# DAC.net
KiCad netlist of a schematic drawn in EAGLE
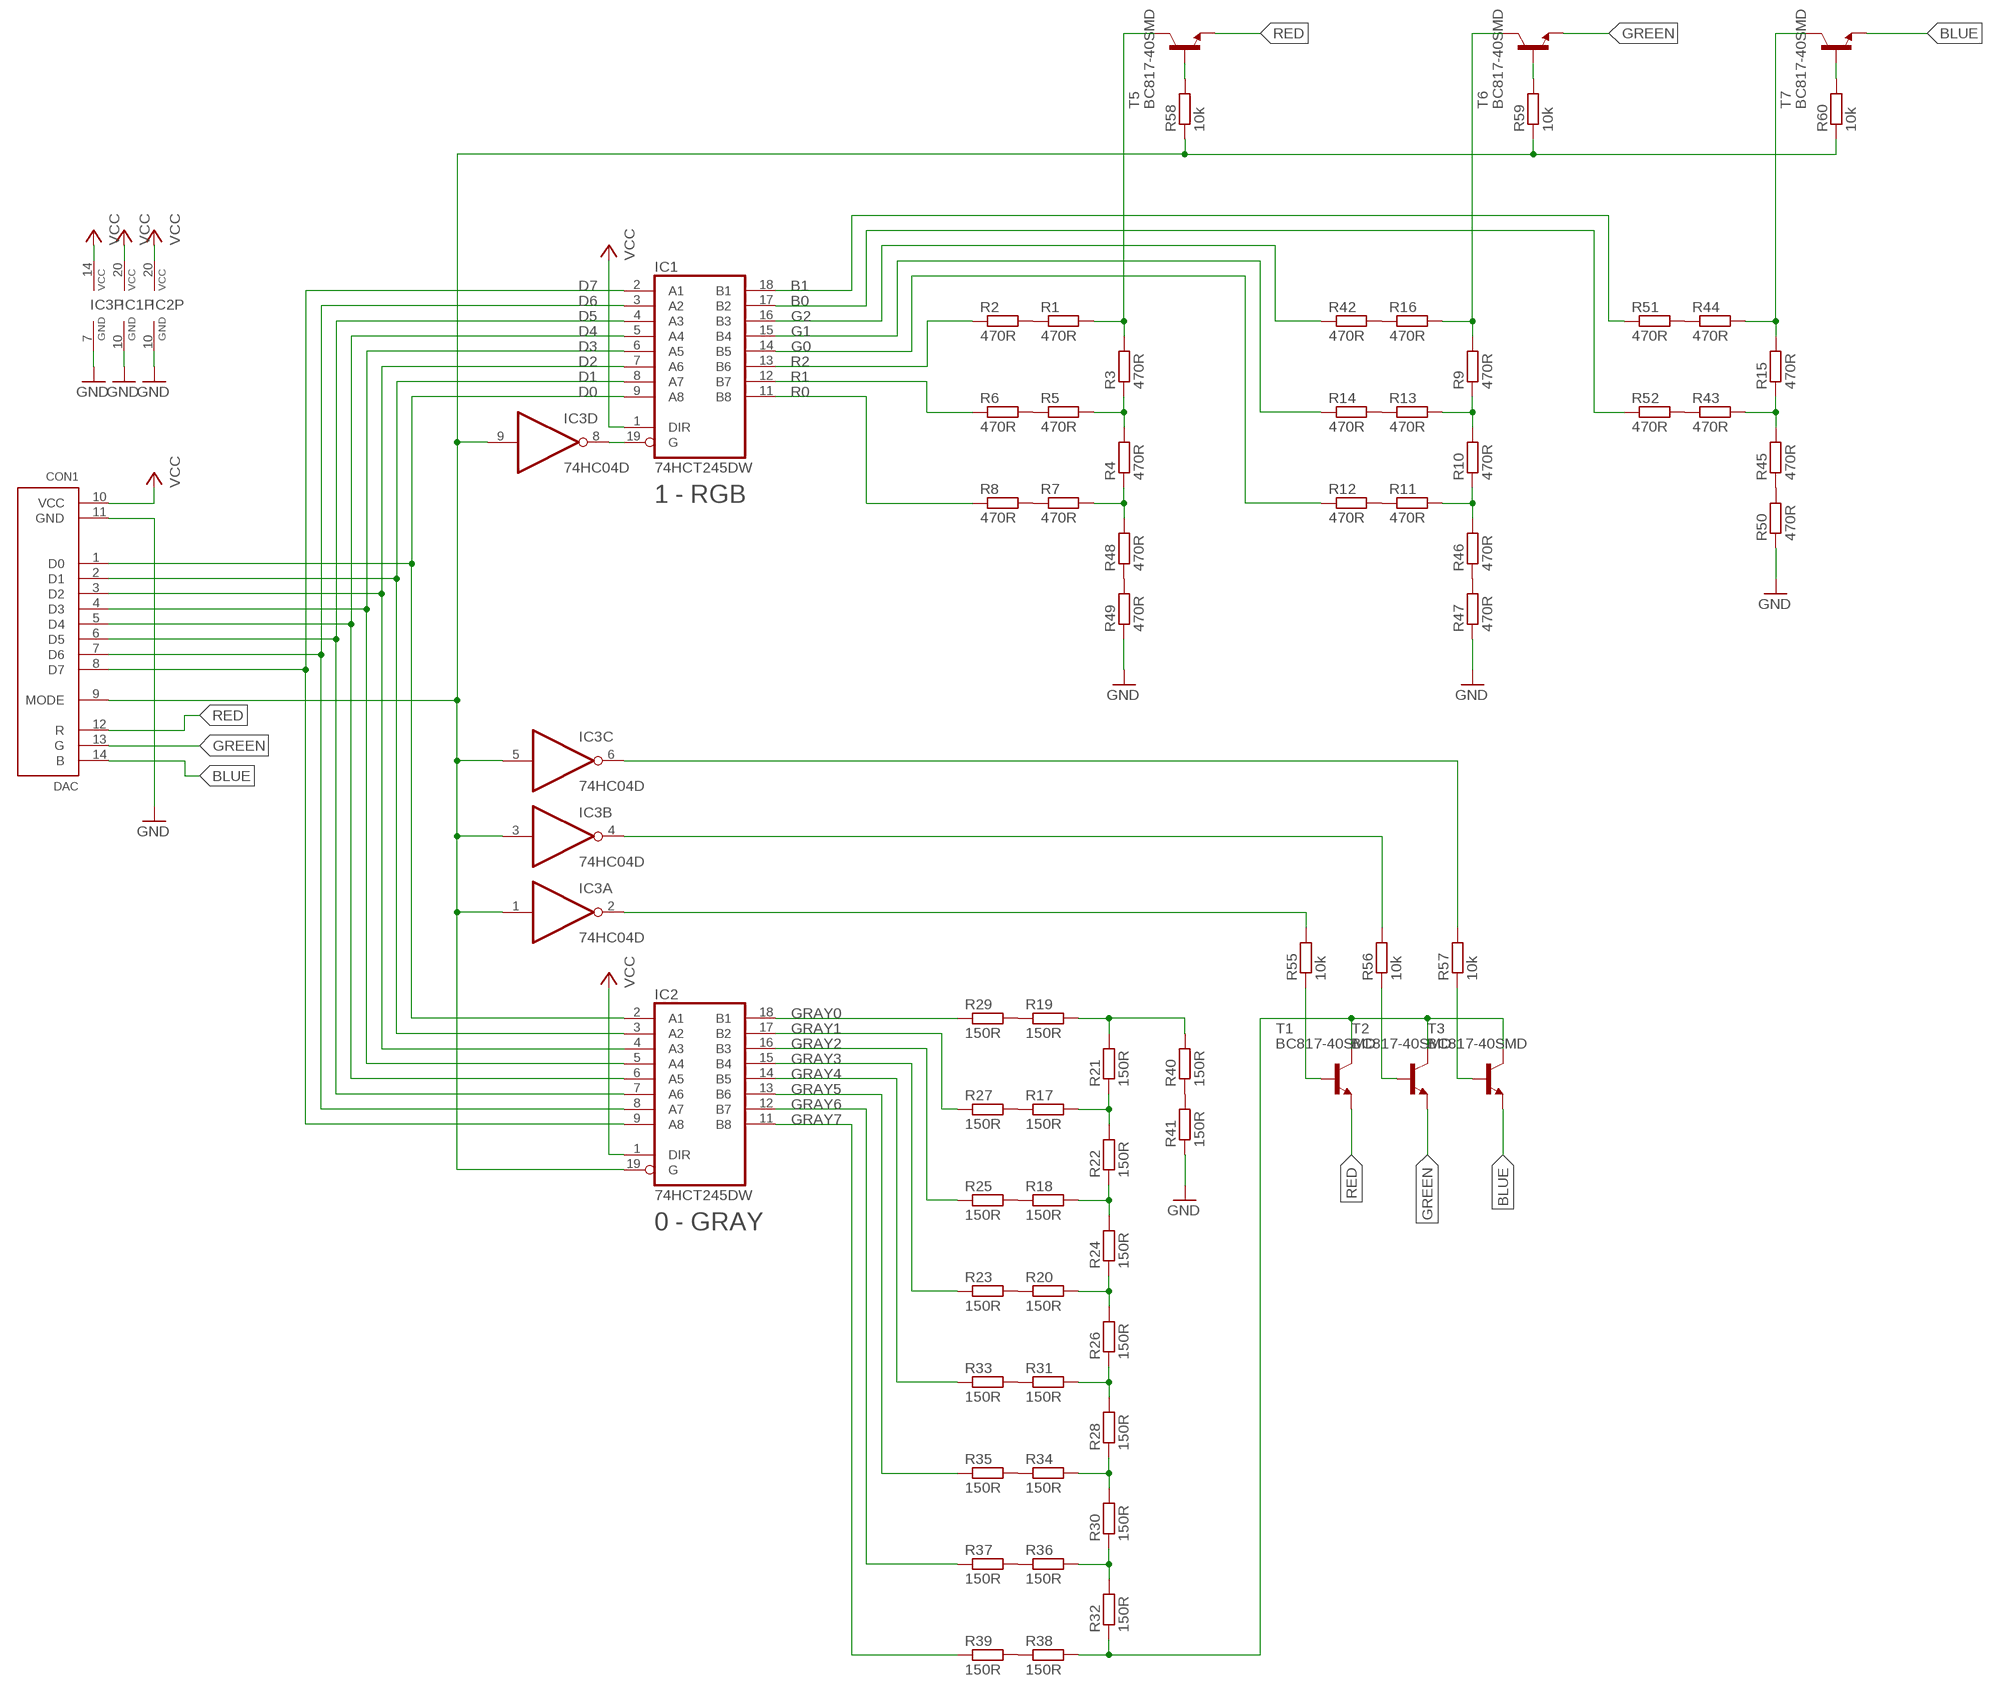
[diagram p0: schematic, sheet 1]

(export (version "E")
  (design (tool "Eeschema 10.0.6"))
  (components
    (comp (ref "CON1")
      (value "DAC")
      (footprint "eagle-import:DAC_CON")
      (libsource (lib "eagle-import") (part "DAC"))
    )
    (comp (ref "IC1")
      (value "74HCT245DW")
      (footprint "eagle-import:SO20W")
      (libsource (lib "eagle-import") (part "74245DWHCT"))
    )
    (comp (ref "IC2")
      (value "74HCT245DW")
      (footprint "eagle-import:SO20W")
      (libsource (lib "eagle-import") (part "74245DWHCT"))
    )
    (comp (ref "IC3")
      (value "74HC04D")
      (footprint "eagle-import:SO14")
      (libsource (lib "eagle-import") (part "7404DHC"))
    )
    (comp (ref "R1")
      (value "470R")
      (footprint "eagle-import:R0603")
      (libsource (lib "eagle-import") (part "R-EU_R0603"))
    )
    (comp (ref "R2")
      (value "470R")
      (footprint "eagle-import:R0603")
      (libsource (lib "eagle-import") (part "R-EU_R0603"))
    )
    (comp (ref "R3")
      (value "470R")
      (footprint "eagle-import:R0603")
      (libsource (lib "eagle-import") (part "R-EU_R0603"))
    )
    (comp (ref "R4")
      (value "470R")
      (footprint "eagle-import:R0603")
      (libsource (lib "eagle-import") (part "R-EU_R0603"))
    )
    (comp (ref "R5")
      (value "470R")
      (footprint "eagle-import:R0603")
      (libsource (lib "eagle-import") (part "R-EU_R0603"))
    )
    (comp (ref "R6")
      (value "470R")
      (footprint "eagle-import:R0603")
      (libsource (lib "eagle-import") (part "R-EU_R0603"))
    )
    (comp (ref "R7")
      (value "470R")
      (footprint "eagle-import:R0603")
      (libsource (lib "eagle-import") (part "R-EU_R0603"))
    )
    (comp (ref "R8")
      (value "470R")
      (footprint "eagle-import:R0603")
      (libsource (lib "eagle-import") (part "R-EU_R0603"))
    )
    (comp (ref "R9")
      (value "470R")
      (footprint "eagle-import:R0603")
      (libsource (lib "eagle-import") (part "R-EU_R0603"))
    )
    (comp (ref "R10")
      (value "470R")
      (footprint "eagle-import:R0603")
      (libsource (lib "eagle-import") (part "R-EU_R0603"))
    )
    (comp (ref "R11")
      (value "470R")
      (footprint "eagle-import:R0603")
      (libsource (lib "eagle-import") (part "R-EU_R0603"))
    )
    (comp (ref "R12")
      (value "470R")
      (footprint "eagle-import:R0603")
      (libsource (lib "eagle-import") (part "R-EU_R0603"))
    )
    (comp (ref "R13")
      (value "470R")
      (footprint "eagle-import:R0603")
      (libsource (lib "eagle-import") (part "R-EU_R0603"))
    )
    (comp (ref "R14")
      (value "470R")
      (footprint "eagle-import:R0603")
      (libsource (lib "eagle-import") (part "R-EU_R0603"))
    )
    (comp (ref "R15")
      (value "470R")
      (footprint "eagle-import:R0603")
      (libsource (lib "eagle-import") (part "R-EU_R0603"))
    )
    (comp (ref "R16")
      (value "470R")
      (footprint "eagle-import:R0603")
      (libsource (lib "eagle-import") (part "R-EU_R0603"))
    )
    (comp (ref "R17")
      (value "150R")
      (footprint "eagle-import:R0603")
      (libsource (lib "eagle-import") (part "R-EU_R0603"))
    )
    (comp (ref "R18")
      (value "150R")
      (footprint "eagle-import:R0603")
      (libsource (lib "eagle-import") (part "R-EU_R0603"))
    )
    (comp (ref "R19")
      (value "150R")
      (footprint "eagle-import:R0603")
      (libsource (lib "eagle-import") (part "R-EU_R0603"))
    )
    (comp (ref "R20")
      (value "150R")
      (footprint "eagle-import:R0603")
      (libsource (lib "eagle-import") (part "R-EU_R0603"))
    )
    (comp (ref "R21")
      (value "150R")
      (footprint "eagle-import:R0603")
      (libsource (lib "eagle-import") (part "R-EU_R0603"))
    )
    (comp (ref "R22")
      (value "150R")
      (footprint "eagle-import:R0603")
      (libsource (lib "eagle-import") (part "R-EU_R0603"))
    )
    (comp (ref "R23")
      (value "150R")
      (footprint "eagle-import:R0603")
      (libsource (lib "eagle-import") (part "R-EU_R0603"))
    )
    (comp (ref "R24")
      (value "150R")
      (footprint "eagle-import:R0603")
      (libsource (lib "eagle-import") (part "R-EU_R0603"))
    )
    (comp (ref "R25")
      (value "150R")
      (footprint "eagle-import:R0603")
      (libsource (lib "eagle-import") (part "R-EU_R0603"))
    )
    (comp (ref "R26")
      (value "150R")
      (footprint "eagle-import:R0603")
      (libsource (lib "eagle-import") (part "R-EU_R0603"))
    )
    (comp (ref "R27")
      (value "150R")
      (footprint "eagle-import:R0603")
      (libsource (lib "eagle-import") (part "R-EU_R0603"))
    )
    (comp (ref "R28")
      (value "150R")
      (footprint "eagle-import:R0603")
      (libsource (lib "eagle-import") (part "R-EU_R0603"))
    )
    (comp (ref "R29")
      (value "150R")
      (footprint "eagle-import:R0603")
      (libsource (lib "eagle-import") (part "R-EU_R0603"))
    )
    (comp (ref "R30")
      (value "150R")
      (footprint "eagle-import:R0603")
      (libsource (lib "eagle-import") (part "R-EU_R0603"))
    )
    (comp (ref "R31")
      (value "150R")
      (footprint "eagle-import:R0603")
      (libsource (lib "eagle-import") (part "R-EU_R0603"))
    )
    (comp (ref "R32")
      (value "150R")
      (footprint "eagle-import:R0603")
      (libsource (lib "eagle-import") (part "R-EU_R0603"))
    )
    (comp (ref "R33")
      (value "150R")
      (footprint "eagle-import:R0603")
      (libsource (lib "eagle-import") (part "R-EU_R0603"))
    )
    (comp (ref "R34")
      (value "150R")
      (footprint "eagle-import:R0603")
      (libsource (lib "eagle-import") (part "R-EU_R0603"))
    )
    (comp (ref "R35")
      (value "150R")
      (footprint "eagle-import:R0603")
      (libsource (lib "eagle-import") (part "R-EU_R0603"))
    )
    (comp (ref "R36")
      (value "150R")
      (footprint "eagle-import:R0603")
      (libsource (lib "eagle-import") (part "R-EU_R0603"))
    )
    (comp (ref "R37")
      (value "150R")
      (footprint "eagle-import:R0603")
      (libsource (lib "eagle-import") (part "R-EU_R0603"))
    )
    (comp (ref "R38")
      (value "150R")
      (footprint "eagle-import:R0603")
      (libsource (lib "eagle-import") (part "R-EU_R0603"))
    )
    (comp (ref "R39")
      (value "150R")
      (footprint "eagle-import:R0603")
      (libsource (lib "eagle-import") (part "R-EU_R0603"))
    )
    (comp (ref "R40")
      (value "150R")
      (footprint "eagle-import:R0603")
      (libsource (lib "eagle-import") (part "R-EU_R0603"))
    )
    (comp (ref "R41")
      (value "150R")
      (footprint "eagle-import:R0603")
      (libsource (lib "eagle-import") (part "R-EU_R0603"))
    )
    (comp (ref "R42")
      (value "470R")
      (footprint "eagle-import:R0603")
      (libsource (lib "eagle-import") (part "R-EU_R0603"))
    )
    (comp (ref "R43")
      (value "470R")
      (footprint "eagle-import:R0603")
      (libsource (lib "eagle-import") (part "R-EU_R0603"))
    )
    (comp (ref "R44")
      (value "470R")
      (footprint "eagle-import:R0603")
      (libsource (lib "eagle-import") (part "R-EU_R0603"))
    )
    (comp (ref "R45")
      (value "470R")
      (footprint "eagle-import:R0603")
      (libsource (lib "eagle-import") (part "R-EU_R0603"))
    )
    (comp (ref "R46")
      (value "470R")
      (footprint "eagle-import:R0603")
      (libsource (lib "eagle-import") (part "R-EU_R0603"))
    )
    (comp (ref "R47")
      (value "470R")
      (footprint "eagle-import:R0603")
      (libsource (lib "eagle-import") (part "R-EU_R0603"))
    )
    (comp (ref "R48")
      (value "470R")
      (footprint "eagle-import:R0603")
      (libsource (lib "eagle-import") (part "R-EU_R0603"))
    )
    (comp (ref "R49")
      (value "470R")
      (footprint "eagle-import:R0603")
      (libsource (lib "eagle-import") (part "R-EU_R0603"))
    )
    (comp (ref "R50")
      (value "470R")
      (footprint "eagle-import:R0603")
      (libsource (lib "eagle-import") (part "R-EU_R0603"))
    )
    (comp (ref "R51")
      (value "470R")
      (footprint "eagle-import:R0603")
      (libsource (lib "eagle-import") (part "R-EU_R0603"))
    )
    (comp (ref "R52")
      (value "470R")
      (footprint "eagle-import:R0603")
      (libsource (lib "eagle-import") (part "R-EU_R0603"))
    )
    (comp (ref "R55")
      (value "10k")
      (footprint "eagle-import:R0603")
      (libsource (lib "eagle-import") (part "R-EU_R0603"))
    )
    (comp (ref "R56")
      (value "10k")
      (footprint "eagle-import:R0603")
      (libsource (lib "eagle-import") (part "R-EU_R0603"))
    )
    (comp (ref "R57")
      (value "10k")
      (footprint "eagle-import:R0603")
      (libsource (lib "eagle-import") (part "R-EU_R0603"))
    )
    (comp (ref "R58")
      (value "10k")
      (footprint "eagle-import:R0603")
      (libsource (lib "eagle-import") (part "R-EU_R0603"))
    )
    (comp (ref "R59")
      (value "10k")
      (footprint "eagle-import:R0603")
      (libsource (lib "eagle-import") (part "R-EU_R0603"))
    )
    (comp (ref "R60")
      (value "10k")
      (footprint "eagle-import:R0603")
      (libsource (lib "eagle-import") (part "R-EU_R0603"))
    )
    (comp (ref "T1")
      (value "BC817-40SMD")
      (footprint "eagle-import:SOT23-BEC")
      (libsource (lib "eagle-import") (part "BC817SMD-40"))
    )
    (comp (ref "T2")
      (value "BC817-40SMD")
      (footprint "eagle-import:SOT23-BEC")
      (libsource (lib "eagle-import") (part "BC817SMD-40"))
    )
    (comp (ref "T3")
      (value "BC817-40SMD")
      (footprint "eagle-import:SOT23-BEC")
      (libsource (lib "eagle-import") (part "BC817SMD-40"))
    )
    (comp (ref "T5")
      (value "BC817-40SMD")
      (footprint "eagle-import:SOT23-BEC")
      (libsource (lib "eagle-import") (part "BC817SMD-40"))
    )
    (comp (ref "T6")
      (value "BC817-40SMD")
      (footprint "eagle-import:SOT23-BEC")
      (libsource (lib "eagle-import") (part "BC817SMD-40"))
    )
    (comp (ref "T7")
      (value "BC817-40SMD")
      (footprint "eagle-import:SOT23-BEC")
      (libsource (lib "eagle-import") (part "BC817SMD-40"))
    )
  )
  (nets
    (net (code "1") (name "/B0") (class "Default")
      (node (ref "IC1") (pin "17") (pinfunction "B2_17") (pintype "bidirectional"))
      (node (ref "R52") (pin "1") (pinfunction "1_1") (pintype "passive"))
    )
    (net (code "2") (name "/B1") (class "Default")
      (node (ref "IC1") (pin "18") (pinfunction "B1_18") (pintype "bidirectional"))
      (node (ref "R51") (pin "1") (pinfunction "1_1") (pintype "passive"))
    )
    (net (code "3") (name "/D0") (class "Default")
      (node (ref "CON1") (pin "1") (pinfunction "D0_1") (pintype "input"))
      (node (ref "IC1") (pin "9") (pinfunction "A8_9") (pintype "bidirectional"))
      (node (ref "IC2") (pin "2") (pinfunction "A1_2") (pintype "bidirectional"))
    )
    (net (code "4") (name "/D1") (class "Default")
      (node (ref "CON1") (pin "2") (pinfunction "D1_2") (pintype "input"))
      (node (ref "IC1") (pin "8") (pinfunction "A7_8") (pintype "bidirectional"))
      (node (ref "IC2") (pin "3") (pinfunction "A2_3") (pintype "bidirectional"))
    )
    (net (code "5") (name "/D2") (class "Default")
      (node (ref "CON1") (pin "3") (pinfunction "D2_3") (pintype "input"))
      (node (ref "IC1") (pin "7") (pinfunction "A6_7") (pintype "bidirectional"))
      (node (ref "IC2") (pin "4") (pinfunction "A3_4") (pintype "bidirectional"))
    )
    (net (code "6") (name "/D3") (class "Default")
      (node (ref "CON1") (pin "4") (pinfunction "D3_4") (pintype "input"))
      (node (ref "IC1") (pin "6") (pinfunction "A5_6") (pintype "bidirectional"))
      (node (ref "IC2") (pin "5") (pinfunction "A4_5") (pintype "bidirectional"))
    )
    (net (code "7") (name "/D4") (class "Default")
      (node (ref "CON1") (pin "5") (pinfunction "D4_5") (pintype "input"))
      (node (ref "IC1") (pin "5") (pinfunction "A4_5") (pintype "bidirectional"))
      (node (ref "IC2") (pin "6") (pinfunction "A5_6") (pintype "bidirectional"))
    )
    (net (code "8") (name "/D5") (class "Default")
      (node (ref "CON1") (pin "6") (pinfunction "D5_6") (pintype "input"))
      (node (ref "IC1") (pin "4") (pinfunction "A3_4") (pintype "bidirectional"))
      (node (ref "IC2") (pin "7") (pinfunction "A6_7") (pintype "bidirectional"))
    )
    (net (code "9") (name "/D6") (class "Default")
      (node (ref "CON1") (pin "7") (pinfunction "D6_7") (pintype "input"))
      (node (ref "IC1") (pin "3") (pinfunction "A2_3") (pintype "bidirectional"))
      (node (ref "IC2") (pin "8") (pinfunction "A7_8") (pintype "bidirectional"))
    )
    (net (code "10") (name "/D7") (class "Default")
      (node (ref "CON1") (pin "8") (pinfunction "D7_8") (pintype "input"))
      (node (ref "IC1") (pin "2") (pinfunction "A1_2") (pintype "bidirectional"))
      (node (ref "IC2") (pin "9") (pinfunction "A8_9") (pintype "bidirectional"))
    )
    (net (code "11") (name "/G0") (class "Default")
      (node (ref "IC1") (pin "14") (pinfunction "B5_14") (pintype "bidirectional"))
      (node (ref "R12") (pin "1") (pinfunction "1_1") (pintype "passive"))
    )
    (net (code "12") (name "/G1") (class "Default")
      (node (ref "IC1") (pin "15") (pinfunction "B4_15") (pintype "bidirectional"))
      (node (ref "R14") (pin "1") (pinfunction "1_1") (pintype "passive"))
    )
    (net (code "13") (name "/G2") (class "Default")
      (node (ref "IC1") (pin "16") (pinfunction "B3_16") (pintype "bidirectional"))
      (node (ref "R42") (pin "1") (pinfunction "1_1") (pintype "passive"))
    )
    (net (code "14") (name "/GRAY0") (class "Default")
      (node (ref "IC2") (pin "18") (pinfunction "B1_18") (pintype "bidirectional"))
      (node (ref "R29") (pin "1") (pinfunction "1_1") (pintype "passive"))
    )
    (net (code "15") (name "/GRAY1") (class "Default")
      (node (ref "IC2") (pin "17") (pinfunction "B2_17") (pintype "bidirectional"))
      (node (ref "R27") (pin "1") (pinfunction "1_1") (pintype "passive"))
    )
    (net (code "16") (name "/GRAY2") (class "Default")
      (node (ref "IC2") (pin "16") (pinfunction "B3_16") (pintype "bidirectional"))
      (node (ref "R25") (pin "1") (pinfunction "1_1") (pintype "passive"))
    )
    (net (code "17") (name "/GRAY3") (class "Default")
      (node (ref "IC2") (pin "15") (pinfunction "B4_15") (pintype "bidirectional"))
      (node (ref "R23") (pin "1") (pinfunction "1_1") (pintype "passive"))
    )
    (net (code "18") (name "/GRAY4") (class "Default")
      (node (ref "IC2") (pin "14") (pinfunction "B5_14") (pintype "bidirectional"))
      (node (ref "R33") (pin "1") (pinfunction "1_1") (pintype "passive"))
    )
    (net (code "19") (name "/GRAY5") (class "Default")
      (node (ref "IC2") (pin "13") (pinfunction "B6_13") (pintype "bidirectional"))
      (node (ref "R35") (pin "1") (pinfunction "1_1") (pintype "passive"))
    )
    (net (code "20") (name "/GRAY6") (class "Default")
      (node (ref "IC2") (pin "12") (pinfunction "B7_12") (pintype "bidirectional"))
      (node (ref "R37") (pin "1") (pinfunction "1_1") (pintype "passive"))
    )
    (net (code "21") (name "/GRAY7") (class "Default")
      (node (ref "IC2") (pin "11") (pinfunction "B8_11") (pintype "bidirectional"))
      (node (ref "R39") (pin "1") (pinfunction "1_1") (pintype "passive"))
    )
    (net (code "22") (name "/R0") (class "Default")
      (node (ref "IC1") (pin "11") (pinfunction "B8_11") (pintype "bidirectional"))
      (node (ref "R8") (pin "1") (pinfunction "1_1") (pintype "passive"))
    )
    (net (code "23") (name "/R1") (class "Default")
      (node (ref "IC1") (pin "12") (pinfunction "B7_12") (pintype "bidirectional"))
      (node (ref "R6") (pin "1") (pinfunction "1_1") (pintype "passive"))
    )
    (net (code "24") (name "/R2") (class "Default")
      (node (ref "IC1") (pin "13") (pinfunction "B6_13") (pintype "bidirectional"))
      (node (ref "R2") (pin "1") (pinfunction "1_1") (pintype "passive"))
    )
    (net (code "25") (name "BLUE") (class "Default")
      (node (ref "CON1") (pin "14") (pinfunction "B_14") (pintype "output"))
      (node (ref "T3") (pin "E") (pinfunction "E_E") (pintype "passive"))
      (node (ref "T7") (pin "E") (pinfunction "E_E") (pintype "passive"))
    )
    (net (code "26") (name "GND") (class "Default")
      (node (ref "CON1") (pin "11") (pinfunction "GND_11") (pintype "power_in"))
      (node (ref "IC1") (pin "10") (pinfunction "GND_10") (pintype "power_in"))
      (node (ref "IC2") (pin "10") (pinfunction "GND_10") (pintype "power_in"))
      (node (ref "IC3") (pin "7") (pinfunction "GND_7") (pintype "power_in"))
      (node (ref "R41") (pin "1") (pinfunction "1_1") (pintype "passive"))
      (node (ref "R47") (pin "1") (pinfunction "1_1") (pintype "passive"))
      (node (ref "R49") (pin "1") (pinfunction "1_1") (pintype "passive"))
      (node (ref "R50") (pin "1") (pinfunction "1_1") (pintype "passive"))
    )
    (net (code "27") (name "GREEN") (class "Default")
      (node (ref "CON1") (pin "13") (pinfunction "G_13") (pintype "output"))
      (node (ref "T2") (pin "E") (pinfunction "E_E") (pintype "passive"))
      (node (ref "T6") (pin "E") (pinfunction "E_E") (pintype "passive"))
    )
    (net (code "28") (name "Net-(CON1-MODE)") (class "Default")
      (node (ref "CON1") (pin "9") (pinfunction "MODE_9") (pintype "input"))
      (node (ref "IC2") (pin "19") (pinfunction "G_19") (pintype "input"))
      (node (ref "IC3") (pin "1") (pinfunction "I_1") (pintype "input"))
      (node (ref "IC3") (pin "3") (pinfunction "I_3") (pintype "input"))
      (node (ref "IC3") (pin "5") (pinfunction "I_5") (pintype "input"))
      (node (ref "IC3") (pin "9") (pinfunction "I_9") (pintype "input"))
      (node (ref "R58") (pin "1") (pinfunction "1_1") (pintype "passive"))
      (node (ref "R59") (pin "1") (pinfunction "1_1") (pintype "passive"))
      (node (ref "R60") (pin "1") (pinfunction "1_1") (pintype "passive"))
    )
    (net (code "29") (name "Net-(IC1A-G)") (class "Default")
      (node (ref "IC1") (pin "19") (pinfunction "G_19") (pintype "input"))
      (node (ref "IC3") (pin "8") (pinfunction "O_8") (pintype "output"))
    )
    (net (code "30") (name "Net-(IC3A-O)") (class "Default")
      (node (ref "IC3") (pin "2") (pinfunction "O_2") (pintype "output"))
      (node (ref "R55") (pin "2") (pinfunction "2_2") (pintype "passive"))
    )
    (net (code "31") (name "Net-(IC3B-O)") (class "Default")
      (node (ref "IC3") (pin "4") (pinfunction "O_4") (pintype "output"))
      (node (ref "R56") (pin "2") (pinfunction "2_2") (pintype "passive"))
    )
    (net (code "32") (name "Net-(IC3C-O)") (class "Default")
      (node (ref "IC3") (pin "6") (pinfunction "O_6") (pintype "output"))
      (node (ref "R57") (pin "2") (pinfunction "2_2") (pintype "passive"))
    )
    (net (code "33") (name "Net-(R1-Pad1)") (class "Default")
      (node (ref "R1") (pin "1") (pinfunction "1_1") (pintype "passive"))
      (node (ref "R2") (pin "2") (pinfunction "2_2") (pintype "passive"))
    )
    (net (code "34") (name "Net-(R1-Pad2)") (class "Default")
      (node (ref "R1") (pin "2") (pinfunction "2_2") (pintype "passive"))
      (node (ref "R3") (pin "2") (pinfunction "2_2") (pintype "passive"))
      (node (ref "T5") (pin "C") (pinfunction "C_C") (pintype "passive"))
    )
    (net (code "35") (name "Net-(R3-Pad1)") (class "Default")
      (node (ref "R3") (pin "1") (pinfunction "1_1") (pintype "passive"))
      (node (ref "R4") (pin "2") (pinfunction "2_2") (pintype "passive"))
      (node (ref "R5") (pin "2") (pinfunction "2_2") (pintype "passive"))
    )
    (net (code "36") (name "Net-(R4-Pad1)") (class "Default")
      (node (ref "R4") (pin "1") (pinfunction "1_1") (pintype "passive"))
      (node (ref "R48") (pin "2") (pinfunction "2_2") (pintype "passive"))
      (node (ref "R7") (pin "2") (pinfunction "2_2") (pintype "passive"))
    )
    (net (code "37") (name "Net-(R5-Pad1)") (class "Default")
      (node (ref "R5") (pin "1") (pinfunction "1_1") (pintype "passive"))
      (node (ref "R6") (pin "2") (pinfunction "2_2") (pintype "passive"))
    )
    (net (code "38") (name "Net-(R7-Pad1)") (class "Default")
      (node (ref "R7") (pin "1") (pinfunction "1_1") (pintype "passive"))
      (node (ref "R8") (pin "2") (pinfunction "2_2") (pintype "passive"))
    )
    (net (code "39") (name "Net-(R10-Pad1)") (class "Default")
      (node (ref "R10") (pin "1") (pinfunction "1_1") (pintype "passive"))
      (node (ref "R11") (pin "2") (pinfunction "2_2") (pintype "passive"))
      (node (ref "R46") (pin "2") (pinfunction "2_2") (pintype "passive"))
    )
    (net (code "40") (name "Net-(R10-Pad2)") (class "Default")
      (node (ref "R10") (pin "2") (pinfunction "2_2") (pintype "passive"))
      (node (ref "R13") (pin "2") (pinfunction "2_2") (pintype "passive"))
      (node (ref "R9") (pin "1") (pinfunction "1_1") (pintype "passive"))
    )
    (net (code "41") (name "Net-(R11-Pad1)") (class "Default")
      (node (ref "R11") (pin "1") (pinfunction "1_1") (pintype "passive"))
      (node (ref "R12") (pin "2") (pinfunction "2_2") (pintype "passive"))
    )
    (net (code "42") (name "Net-(R13-Pad1)") (class "Default")
      (node (ref "R13") (pin "1") (pinfunction "1_1") (pintype "passive"))
      (node (ref "R14") (pin "2") (pinfunction "2_2") (pintype "passive"))
    )
    (net (code "43") (name "Net-(R15-Pad1)") (class "Default")
      (node (ref "R15") (pin "1") (pinfunction "1_1") (pintype "passive"))
      (node (ref "R43") (pin "2") (pinfunction "2_2") (pintype "passive"))
      (node (ref "R45") (pin "2") (pinfunction "2_2") (pintype "passive"))
    )
    (net (code "44") (name "Net-(R15-Pad2)") (class "Default")
      (node (ref "R15") (pin "2") (pinfunction "2_2") (pintype "passive"))
      (node (ref "R44") (pin "2") (pinfunction "2_2") (pintype "passive"))
      (node (ref "T7") (pin "C") (pinfunction "C_C") (pintype "passive"))
    )
    (net (code "45") (name "Net-(R16-Pad1)") (class "Default")
      (node (ref "R16") (pin "1") (pinfunction "1_1") (pintype "passive"))
      (node (ref "R42") (pin "2") (pinfunction "2_2") (pintype "passive"))
    )
    (net (code "46") (name "Net-(R16-Pad2)") (class "Default")
      (node (ref "R16") (pin "2") (pinfunction "2_2") (pintype "passive"))
      (node (ref "R9") (pin "2") (pinfunction "2_2") (pintype "passive"))
      (node (ref "T6") (pin "C") (pinfunction "C_C") (pintype "passive"))
    )
    (net (code "47") (name "Net-(R17-Pad1)") (class "Default")
      (node (ref "R17") (pin "1") (pinfunction "1_1") (pintype "passive"))
      (node (ref "R27") (pin "2") (pinfunction "2_2") (pintype "passive"))
    )
    (net (code "48") (name "Net-(R17-Pad2)") (class "Default")
      (node (ref "R17") (pin "2") (pinfunction "2_2") (pintype "passive"))
      (node (ref "R21") (pin "1") (pinfunction "1_1") (pintype "passive"))
      (node (ref "R22") (pin "2") (pinfunction "2_2") (pintype "passive"))
    )
    (net (code "49") (name "Net-(R18-Pad1)") (class "Default")
      (node (ref "R18") (pin "1") (pinfunction "1_1") (pintype "passive"))
      (node (ref "R25") (pin "2") (pinfunction "2_2") (pintype "passive"))
    )
    (net (code "50") (name "Net-(R18-Pad2)") (class "Default")
      (node (ref "R18") (pin "2") (pinfunction "2_2") (pintype "passive"))
      (node (ref "R22") (pin "1") (pinfunction "1_1") (pintype "passive"))
      (node (ref "R24") (pin "2") (pinfunction "2_2") (pintype "passive"))
    )
    (net (code "51") (name "Net-(R19-Pad1)") (class "Default")
      (node (ref "R19") (pin "1") (pinfunction "1_1") (pintype "passive"))
      (node (ref "R29") (pin "2") (pinfunction "2_2") (pintype "passive"))
    )
    (net (code "52") (name "Net-(R19-Pad2)") (class "Default")
      (node (ref "R19") (pin "2") (pinfunction "2_2") (pintype "passive"))
      (node (ref "R21") (pin "2") (pinfunction "2_2") (pintype "passive"))
      (node (ref "R40") (pin "2") (pinfunction "2_2") (pintype "passive"))
    )
    (net (code "53") (name "Net-(R20-Pad1)") (class "Default")
      (node (ref "R20") (pin "1") (pinfunction "1_1") (pintype "passive"))
      (node (ref "R23") (pin "2") (pinfunction "2_2") (pintype "passive"))
    )
    (net (code "54") (name "Net-(R20-Pad2)") (class "Default")
      (node (ref "R20") (pin "2") (pinfunction "2_2") (pintype "passive"))
      (node (ref "R24") (pin "1") (pinfunction "1_1") (pintype "passive"))
      (node (ref "R26") (pin "2") (pinfunction "2_2") (pintype "passive"))
    )
    (net (code "55") (name "Net-(R26-Pad1)") (class "Default")
      (node (ref "R26") (pin "1") (pinfunction "1_1") (pintype "passive"))
      (node (ref "R28") (pin "2") (pinfunction "2_2") (pintype "passive"))
      (node (ref "R31") (pin "2") (pinfunction "2_2") (pintype "passive"))
    )
    (net (code "56") (name "Net-(R28-Pad1)") (class "Default")
      (node (ref "R28") (pin "1") (pinfunction "1_1") (pintype "passive"))
      (node (ref "R30") (pin "2") (pinfunction "2_2") (pintype "passive"))
      (node (ref "R34") (pin "2") (pinfunction "2_2") (pintype "passive"))
    )
    (net (code "57") (name "Net-(R30-Pad1)") (class "Default")
      (node (ref "R30") (pin "1") (pinfunction "1_1") (pintype "passive"))
      (node (ref "R32") (pin "2") (pinfunction "2_2") (pintype "passive"))
      (node (ref "R36") (pin "2") (pinfunction "2_2") (pintype "passive"))
    )
    (net (code "58") (name "Net-(R31-Pad1)") (class "Default")
      (node (ref "R31") (pin "1") (pinfunction "1_1") (pintype "passive"))
      (node (ref "R33") (pin "2") (pinfunction "2_2") (pintype "passive"))
    )
    (net (code "59") (name "Net-(R32-Pad1)") (class "Default")
      (node (ref "R32") (pin "1") (pinfunction "1_1") (pintype "passive"))
      (node (ref "R38") (pin "2") (pinfunction "2_2") (pintype "passive"))
      (node (ref "T1") (pin "C") (pinfunction "C_C") (pintype "passive"))
      (node (ref "T2") (pin "C") (pinfunction "C_C") (pintype "passive"))
      (node (ref "T3") (pin "C") (pinfunction "C_C") (pintype "passive"))
    )
    (net (code "60") (name "Net-(R34-Pad1)") (class "Default")
      (node (ref "R34") (pin "1") (pinfunction "1_1") (pintype "passive"))
      (node (ref "R35") (pin "2") (pinfunction "2_2") (pintype "passive"))
    )
    (net (code "61") (name "Net-(R36-Pad1)") (class "Default")
      (node (ref "R36") (pin "1") (pinfunction "1_1") (pintype "passive"))
      (node (ref "R37") (pin "2") (pinfunction "2_2") (pintype "passive"))
    )
    (net (code "62") (name "Net-(R38-Pad1)") (class "Default")
      (node (ref "R38") (pin "1") (pinfunction "1_1") (pintype "passive"))
      (node (ref "R39") (pin "2") (pinfunction "2_2") (pintype "passive"))
    )
    (net (code "63") (name "Net-(R40-Pad1)") (class "Default")
      (node (ref "R40") (pin "1") (pinfunction "1_1") (pintype "passive"))
      (node (ref "R41") (pin "2") (pinfunction "2_2") (pintype "passive"))
    )
    (net (code "64") (name "Net-(R43-Pad1)") (class "Default")
      (node (ref "R43") (pin "1") (pinfunction "1_1") (pintype "passive"))
      (node (ref "R52") (pin "2") (pinfunction "2_2") (pintype "passive"))
    )
    (net (code "65") (name "Net-(R44-Pad1)") (class "Default")
      (node (ref "R44") (pin "1") (pinfunction "1_1") (pintype "passive"))
      (node (ref "R51") (pin "2") (pinfunction "2_2") (pintype "passive"))
    )
    (net (code "66") (name "Net-(R45-Pad1)") (class "Default")
      (node (ref "R45") (pin "1") (pinfunction "1_1") (pintype "passive"))
      (node (ref "R50") (pin "2") (pinfunction "2_2") (pintype "passive"))
    )
    (net (code "67") (name "Net-(R46-Pad1)") (class "Default")
      (node (ref "R46") (pin "1") (pinfunction "1_1") (pintype "passive"))
      (node (ref "R47") (pin "2") (pinfunction "2_2") (pintype "passive"))
    )
    (net (code "68") (name "Net-(R48-Pad1)") (class "Default")
      (node (ref "R48") (pin "1") (pinfunction "1_1") (pintype "passive"))
      (node (ref "R49") (pin "2") (pinfunction "2_2") (pintype "passive"))
    )
    (net (code "69") (name "Net-(R55-Pad1)") (class "Default")
      (node (ref "R55") (pin "1") (pinfunction "1_1") (pintype "passive"))
      (node (ref "T1") (pin "B") (pinfunction "B_B") (pintype "passive"))
    )
    (net (code "70") (name "Net-(R56-Pad1)") (class "Default")
      (node (ref "R56") (pin "1") (pinfunction "1_1") (pintype "passive"))
      (node (ref "T2") (pin "B") (pinfunction "B_B") (pintype "passive"))
    )
    (net (code "71") (name "Net-(R57-Pad1)") (class "Default")
      (node (ref "R57") (pin "1") (pinfunction "1_1") (pintype "passive"))
      (node (ref "T3") (pin "B") (pinfunction "B_B") (pintype "passive"))
    )
    (net (code "72") (name "Net-(R58-Pad2)") (class "Default")
      (node (ref "R58") (pin "2") (pinfunction "2_2") (pintype "passive"))
      (node (ref "T5") (pin "B") (pinfunction "B_B") (pintype "passive"))
    )
    (net (code "73") (name "Net-(R59-Pad2)") (class "Default")
      (node (ref "R59") (pin "2") (pinfunction "2_2") (pintype "passive"))
      (node (ref "T6") (pin "B") (pinfunction "B_B") (pintype "passive"))
    )
    (net (code "74") (name "Net-(R60-Pad2)") (class "Default")
      (node (ref "R60") (pin "2") (pinfunction "2_2") (pintype "passive"))
      (node (ref "T7") (pin "B") (pinfunction "B_B") (pintype "passive"))
    )
    (net (code "75") (name "RED") (class "Default")
      (node (ref "CON1") (pin "12") (pinfunction "R_12") (pintype "output"))
      (node (ref "T1") (pin "E") (pinfunction "E_E") (pintype "passive"))
      (node (ref "T5") (pin "E") (pinfunction "E_E") (pintype "passive"))
    )
    (net (code "76") (name "VCC") (class "Default")
      (node (ref "CON1") (pin "10") (pinfunction "VCC_10") (pintype "power_in"))
      (node (ref "IC1") (pin "1") (pinfunction "DIR_1") (pintype "input"))
      (node (ref "IC1") (pin "20") (pinfunction "VCC_20") (pintype "power_in"))
      (node (ref "IC2") (pin "1") (pinfunction "DIR_1") (pintype "input"))
      (node (ref "IC2") (pin "20") (pinfunction "VCC_20") (pintype "power_in"))
      (node (ref "IC3") (pin "14") (pinfunction "VCC_14") (pintype "power_in"))
    )
  )
)
